# float002.net
KiCad netlist of a schematic drawn in EAGLE
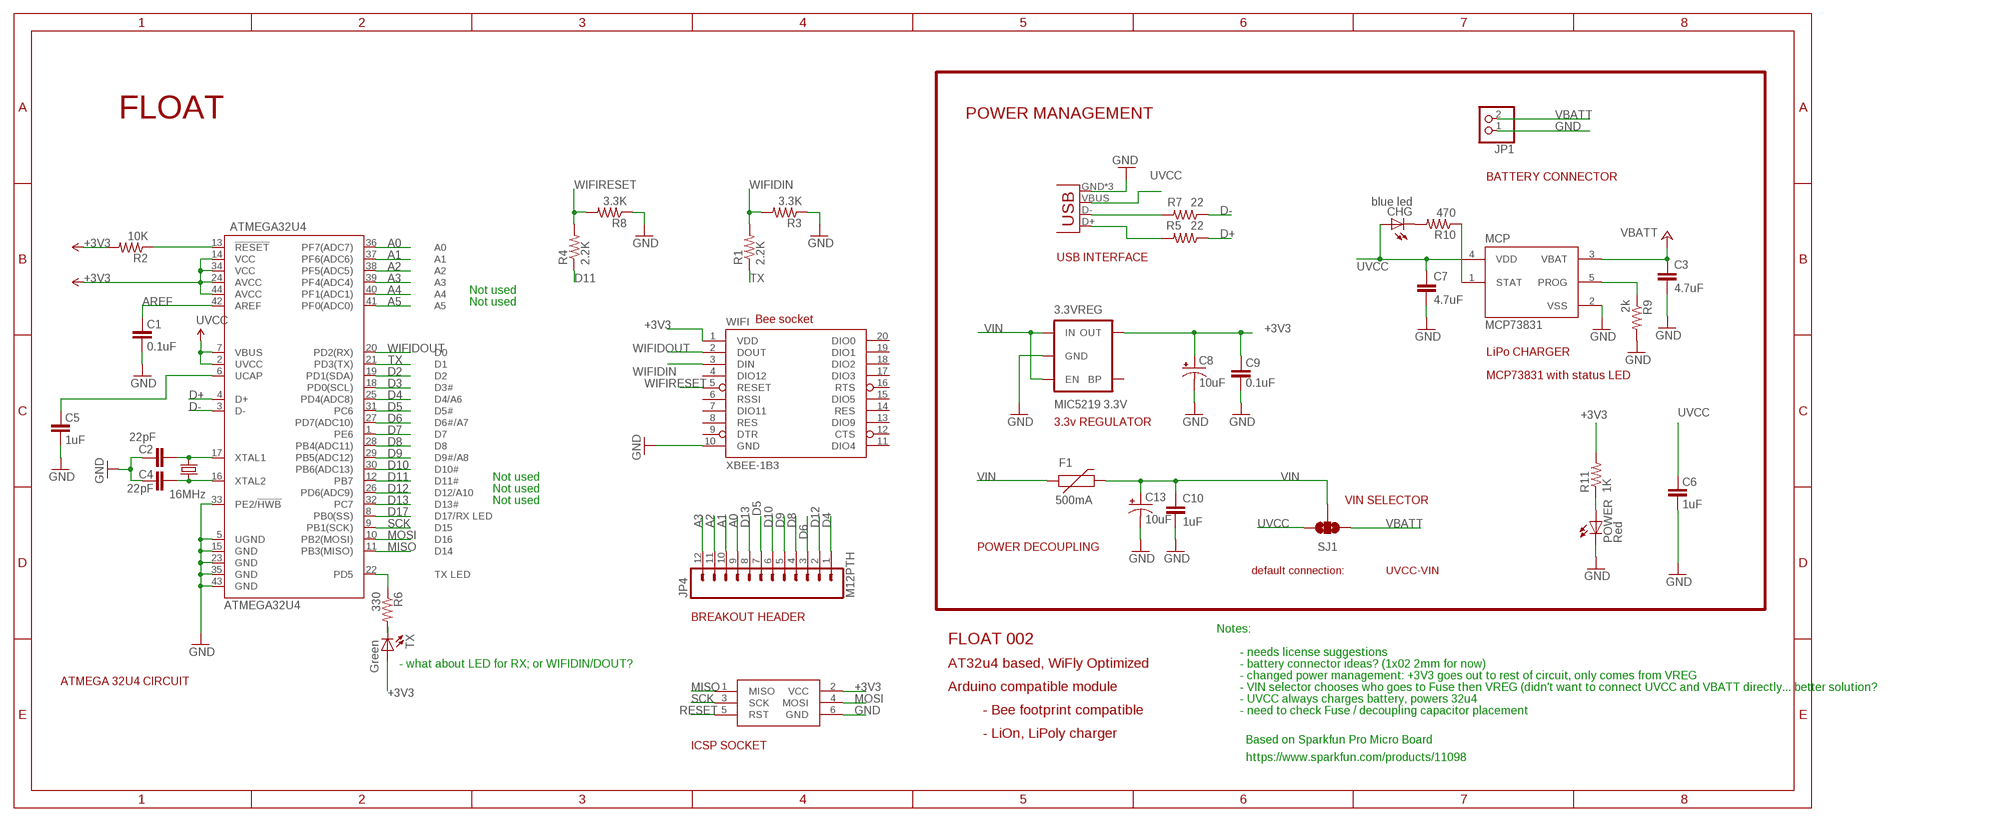
[diagram p0: schematic, sheet 1]

(export (version "E")
  (design (tool "Eeschema 10.0.6"))
  (components
    (comp (ref "3.3VREG")
      (value "MIC5219 3.3V")
      (footprint "eagle-import:SOT23-5")
      (libsource (lib "eagle-import") (part "V_REG_MIC52193.3V"))
    )
    (comp (ref "ATMEGA32U4")
      (value "ATMEGA32U4")
      (footprint "eagle-import:SPARKFUN-DIGITALIC_TQFP44")
      (libsource (lib "eagle-import") (part "ATMEGA32U4TQFP"))
    )
    (comp (ref "C1")
      (value "0.1uF")
      (footprint "eagle-import:0402-CAP")
      (libsource (lib "eagle-import") (part "CAP0402-CAP"))
    )
    (comp (ref "C2")
      (value "22pF")
      (footprint "eagle-import:0402-CAP")
      (libsource (lib "eagle-import") (part "CAP0402-CAP"))
    )
    (comp (ref "C3")
      (value "4.7uF")
      (footprint "eagle-import:0402-CAP")
      (libsource (lib "eagle-import") (part ".1UF-CER"))
    )
    (comp (ref "C4")
      (value "22pF")
      (footprint "eagle-import:0402-CAP")
      (libsource (lib "eagle-import") (part "CAP0402-CAP"))
    )
    (comp (ref "C5")
      (value "1uF")
      (footprint "eagle-import:0402-CAP")
      (libsource (lib "eagle-import") (part "CAP0402-CAP"))
    )
    (comp (ref "C6")
      (value "1uF")
      (footprint "eagle-import:0402-CAP")
      (libsource (lib "eagle-import") (part "CAP0402-CAP"))
    )
    (comp (ref "C7")
      (value "4.7uF")
      (footprint "eagle-import:0402-CAP")
      (libsource (lib "eagle-import") (part ".1UF-CER"))
    )
    (comp (ref "C8")
      (value "10uF")
      (footprint "eagle-import:EIA3216")
      (libsource (lib "eagle-import") (part "CAP_POL1206"))
    )
    (comp (ref "C9")
      (value "0.1uF")
      (footprint "eagle-import:0402-CAP")
      (libsource (lib "eagle-import") (part "CAP0402-CAP"))
    )
    (comp (ref "C10")
      (value "1uF")
      (footprint "eagle-import:0402-CAP")
      (libsource (lib "eagle-import") (part "CAP0402-CAP"))
    )
    (comp (ref "C13")
      (value "10uF")
      (footprint "eagle-import:EIA3216")
      (libsource (lib "eagle-import") (part "CAP_POL1206"))
    )
    (comp (ref "CHG")
      (value "blue led")
      (footprint "eagle-import:CHIP-LED0805")
      (libsource (lib "eagle-import") (part "LEDCHIP-LED0805"))
    )
    (comp (ref "F1")
      (value "500mA")
      (footprint "eagle-import:PTC-1206")
      (libsource (lib "eagle-import") (part "PTCSMD"))
    )
    (comp (ref "ISP1")
      (value "AVRISP-6")
      (footprint "eagle-import:AVRISP")
      (libsource (lib "eagle-import") (part "AVRISP-6"))
    )
    (comp (ref "JP1")
      (value "PINHD-1X2")
      (footprint "eagle-import:1X02")
      (libsource (lib "eagle-import") (part "PINHD-1X2"))
    )
    (comp (ref "JP4")
      (value "M12PTH")
      (footprint "eagle-import:1X12")
      (libsource (lib "eagle-import") (part "M12PTH"))
    )
    (comp (ref "MCP")
      (value "MCP73831")
      (footprint "eagle-import:SOT23-5")
      (libsource (lib "eagle-import") (part "MCP73831"))
    )
    (comp (ref "POWER")
      (value "Red")
      (footprint "eagle-import:LED-0603")
      (libsource (lib "eagle-import") (part "LED0603"))
    )
    (comp (ref "R1")
      (value "2.2K")
      (footprint "eagle-import:0402-RES")
      (libsource (lib "eagle-import") (part "RESISTOR0402-RES"))
    )
    (comp (ref "R2")
      (value "10K")
      (footprint "eagle-import:0402-RES")
      (libsource (lib "eagle-import") (part "RESISTOR0402-RES"))
    )
    (comp (ref "R3")
      (value "3.3K")
      (footprint "eagle-import:0402-RES")
      (libsource (lib "eagle-import") (part "RESISTOR0402-RES"))
    )
    (comp (ref "R4")
      (value "2.2K")
      (footprint "eagle-import:0402-RES")
      (libsource (lib "eagle-import") (part "RESISTOR0402-RES"))
    )
    (comp (ref "R5")
      (value "22")
      (footprint "eagle-import:0402-RES")
      (libsource (lib "eagle-import") (part "RESISTOR0402-RES"))
    )
    (comp (ref "R6")
      (value "330")
      (footprint "eagle-import:0402-RES")
      (libsource (lib "eagle-import") (part "RESISTOR0402-RES"))
    )
    (comp (ref "R7")
      (value "22")
      (footprint "eagle-import:0402-RES")
      (libsource (lib "eagle-import") (part "RESISTOR0402-RES"))
    )
    (comp (ref "R8")
      (value "3.3K")
      (footprint "eagle-import:0402-RES")
      (libsource (lib "eagle-import") (part "RESISTOR0402-RES"))
    )
    (comp (ref "R9")
      (value "2k")
      (footprint "eagle-import:0402-RES")
      (libsource (lib "eagle-import") (part "SparkFun-Resistors_RESISTOR0402-RES"))
    )
    (comp (ref "R10")
      (value "470")
      (footprint "eagle-import:0402-RES")
      (libsource (lib "eagle-import") (part "SparkFun-Resistors_RESISTOR0402-RES"))
    )
    (comp (ref "R11")
      (value "1K")
      (footprint "eagle-import:0402-RES")
      (libsource (lib "eagle-import") (part "RESISTOR0402-RES"))
    )
    (comp (ref "SJ1")
      (value "SOLDERJUMPER_2WAYPASTE1&2")
      (footprint "eagle-import:SJ_3_PASTE1&2")
      (libsource (lib "eagle-import") (part "SOLDERJUMPER_2WAYPASTE1&2"))
    )
    (comp (ref "TX")
      (value "Green")
      (footprint "eagle-import:LED-0603")
      (libsource (lib "eagle-import") (part "LED0603"))
    )
    (comp (ref "WIFI")
      (value "XBEE-1B3")
      (footprint "eagle-import:XBEE-SMD")
      (libsource (lib "eagle-import") (part "XBEE-1B3"))
    )
    (comp (ref "X2")
      (value "USB-MICROB")
      (footprint "eagle-import:USB-MICROB")
      (libsource (lib "eagle-import") (part "USB-MICROB"))
    )
    (comp (ref "Y1")
      (value "16MHz")
      (footprint "eagle-import:CRYSTAL-SMD-5X3")
      (libsource (lib "eagle-import") (part "CRYSTAL5X3"))
    )
  )
  (nets
    (net (code "1") (name "/A0") (class "Default")
      (node (ref "ATMEGA32U4") (pin "36") (pinfunction "PF7(ADC7)_36") (pintype "bidirectional"))
      (node (ref "JP4") (pin "9") (pinfunction "9_9") (pintype "passive"))
    )
    (net (code "2") (name "/A1") (class "Default")
      (node (ref "ATMEGA32U4") (pin "37") (pinfunction "PF6(ADC6)_37") (pintype "bidirectional"))
      (node (ref "JP4") (pin "10") (pinfunction "10_10") (pintype "passive"))
    )
    (net (code "3") (name "/A2") (class "Default")
      (node (ref "ATMEGA32U4") (pin "38") (pinfunction "PF5(ADC5)_38") (pintype "bidirectional"))
      (node (ref "JP4") (pin "11") (pinfunction "11_11") (pintype "passive"))
    )
    (net (code "4") (name "/A3") (class "Default")
      (node (ref "ATMEGA32U4") (pin "39") (pinfunction "PF4(ADC4)_39") (pintype "bidirectional"))
      (node (ref "JP4") (pin "12") (pinfunction "12_12") (pintype "passive"))
    )
    (net (code "5") (name "/A4") (class "Default")
      (node (ref "ATMEGA32U4") (pin "40") (pinfunction "PF1(ADC1)_40") (pintype "bidirectional"))
    )
    (net (code "6") (name "/A5") (class "Default")
      (node (ref "ATMEGA32U4") (pin "41") (pinfunction "PF0(ADC0)_41") (pintype "bidirectional"))
    )
    (net (code "7") (name "/AREF") (class "Default")
      (node (ref "ATMEGA32U4") (pin "42") (pinfunction "AREF_42") (pintype "bidirectional"))
      (node (ref "C1") (pin "2") (pinfunction "2_2") (pintype "passive"))
    )
    (net (code "8") (name "/D+") (class "Default")
      (node (ref "ATMEGA32U4") (pin "4") (pinfunction "D+_4") (pintype "bidirectional"))
      (node (ref "R5") (pin "1") (pinfunction "1_1") (pintype "passive"))
    )
    (net (code "9") (name "/D-") (class "Default")
      (node (ref "ATMEGA32U4") (pin "3") (pinfunction "D-_3") (pintype "bidirectional"))
      (node (ref "R7") (pin "1") (pinfunction "1_1") (pintype "passive"))
    )
    (net (code "10") (name "/D2") (class "Default")
      (node (ref "ATMEGA32U4") (pin "19") (pinfunction "PD1(SDA)_19") (pintype "bidirectional"))
    )
    (net (code "11") (name "/D3") (class "Default")
      (node (ref "ATMEGA32U4") (pin "18") (pinfunction "PD0(SCL)_18") (pintype "bidirectional"))
    )
    (net (code "12") (name "/D4") (class "Default")
      (node (ref "ATMEGA32U4") (pin "25") (pinfunction "PD4(ADC8)_25") (pintype "bidirectional"))
      (node (ref "JP4") (pin "1") (pinfunction "1_1") (pintype "passive"))
    )
    (net (code "13") (name "/D5") (class "Default")
      (node (ref "ATMEGA32U4") (pin "31") (pinfunction "PC6_31") (pintype "bidirectional"))
      (node (ref "JP4") (pin "7") (pinfunction "7_7") (pintype "passive"))
    )
    (net (code "14") (name "/D6") (class "Default")
      (node (ref "ATMEGA32U4") (pin "27") (pinfunction "PD7(ADC10)_27") (pintype "bidirectional"))
      (node (ref "JP4") (pin "3") (pinfunction "3_3") (pintype "passive"))
    )
    (net (code "15") (name "/D7") (class "Default")
      (node (ref "ATMEGA32U4") (pin "1") (pinfunction "PE6_1") (pintype "bidirectional"))
    )
    (net (code "16") (name "/D8") (class "Default")
      (node (ref "ATMEGA32U4") (pin "28") (pinfunction "PB4(ADC11)_28") (pintype "bidirectional"))
      (node (ref "JP4") (pin "4") (pinfunction "4_4") (pintype "passive"))
    )
    (net (code "17") (name "/D9") (class "Default")
      (node (ref "ATMEGA32U4") (pin "29") (pinfunction "PB5(ADC12)_29") (pintype "bidirectional"))
      (node (ref "JP4") (pin "5") (pinfunction "5_5") (pintype "passive"))
    )
    (net (code "18") (name "/D10") (class "Default")
      (node (ref "ATMEGA32U4") (pin "30") (pinfunction "PB6(ADC13)_30") (pintype "bidirectional"))
      (node (ref "JP4") (pin "6") (pinfunction "6_6") (pintype "passive"))
    )
    (net (code "19") (name "/D11") (class "Default")
      (node (ref "ATMEGA32U4") (pin "12") (pinfunction "PB7_12") (pintype "bidirectional"))
      (node (ref "R4") (pin "1") (pinfunction "1_1") (pintype "passive"))
    )
    (net (code "20") (name "/D12") (class "Default")
      (node (ref "ATMEGA32U4") (pin "26") (pinfunction "PD6(ADC9)_26") (pintype "bidirectional"))
      (node (ref "JP4") (pin "2") (pinfunction "2_2") (pintype "passive"))
    )
    (net (code "21") (name "/D13") (class "Default")
      (node (ref "ATMEGA32U4") (pin "32") (pinfunction "PC7_32") (pintype "bidirectional"))
      (node (ref "JP4") (pin "8") (pinfunction "8_8") (pintype "passive"))
    )
    (net (code "22") (name "/D17") (class "Default")
      (node (ref "ATMEGA32U4") (pin "8") (pinfunction "PB0(SS)_8") (pintype "bidirectional"))
    )
    (net (code "23") (name "/MISO") (class "Default")
      (node (ref "ATMEGA32U4") (pin "11") (pinfunction "PB3(MISO)_11") (pintype "bidirectional"))
      (node (ref "ISP1") (pin "1") (pinfunction "MISO_1") (pintype "input"))
    )
    (net (code "24") (name "/MOSI") (class "Default")
      (node (ref "ATMEGA32U4") (pin "10") (pinfunction "PB2(MOSI)_10") (pintype "bidirectional"))
      (node (ref "ISP1") (pin "4") (pinfunction "MOSI_4") (pintype "output"))
    )
    (net (code "25") (name "/RESET") (class "Default")
      (node (ref "ATMEGA32U4") (pin "13") (pinfunction "~{RESET}_13") (pintype "bidirectional"))
      (node (ref "ISP1") (pin "5") (pinfunction "RST_5") (pintype "output"))
      (node (ref "R2") (pin "1") (pinfunction "1_1") (pintype "passive"))
    )
    (net (code "26") (name "/SCK") (class "Default")
      (node (ref "ATMEGA32U4") (pin "9") (pinfunction "PB1(SCK)_9") (pintype "bidirectional"))
      (node (ref "ISP1") (pin "3") (pinfunction "SCK_3") (pintype "output"))
    )
    (net (code "27") (name "/TX") (class "Default")
      (node (ref "ATMEGA32U4") (pin "21") (pinfunction "PD3(TX)_21") (pintype "bidirectional"))
      (node (ref "R1") (pin "1") (pinfunction "1_1") (pintype "passive"))
    )
    (net (code "28") (name "/VIN") (class "Default")
      (node (ref "3.3VREG") (pin "1") (pinfunction "IN_1") (pintype "input"))
      (node (ref "3.3VREG") (pin "3") (pinfunction "EN_3") (pintype "input"))
      (node (ref "C10") (pin "1") (pinfunction "1_1") (pintype "passive"))
      (node (ref "C13") (pin "A") (pinfunction "+_A") (pintype "passive"))
      (node (ref "F1") (pin "1") (pinfunction "1_1") (pintype "bidirectional"))
      (node (ref "F1") (pin "2") (pinfunction "2_2") (pintype "bidirectional"))
      (node (ref "SJ1") (pin "2") (pinfunction "2_2") (pintype "passive"))
    )
    (net (code "29") (name "/WIFIDIN") (class "Default")
      (node (ref "R1") (pin "2") (pinfunction "2_2") (pintype "passive"))
      (node (ref "R3") (pin "2") (pinfunction "2_2") (pintype "passive"))
      (node (ref "WIFI") (pin "3") (pinfunction "DIN_3") (pintype "input"))
    )
    (net (code "30") (name "/WIFIDOUT") (class "Default")
      (node (ref "ATMEGA32U4") (pin "20") (pinfunction "PD2(RX)_20") (pintype "bidirectional"))
      (node (ref "WIFI") (pin "2") (pinfunction "DOUT_2") (pintype "output"))
    )
    (net (code "31") (name "/WIFIRESET") (class "Default")
      (node (ref "R4") (pin "2") (pinfunction "2_2") (pintype "passive"))
      (node (ref "R8") (pin "2") (pinfunction "2_2") (pintype "passive"))
      (node (ref "WIFI") (pin "5") (pinfunction "RESET_5") (pintype "input"))
    )
    (net (code "32") (name "GND") (class "Default")
      (node (ref "3.3VREG") (pin "2") (pinfunction "GND_2") (pintype "input"))
      (node (ref "ATMEGA32U4") (pin "15") (pinfunction "GND_15") (pintype "bidirectional"))
      (node (ref "ATMEGA32U4") (pin "23") (pinfunction "GND_23") (pintype "bidirectional"))
      (node (ref "ATMEGA32U4") (pin "33") (pinfunction "PE2/~{HWB}_33") (pintype "bidirectional"))
      (node (ref "ATMEGA32U4") (pin "35") (pinfunction "GND_35") (pintype "bidirectional"))
      (node (ref "ATMEGA32U4") (pin "43") (pinfunction "GND_43") (pintype "bidirectional"))
      (node (ref "ATMEGA32U4") (pin "5") (pinfunction "UGND_5") (pintype "bidirectional"))
      (node (ref "C1") (pin "1") (pinfunction "1_1") (pintype "passive"))
      (node (ref "C10") (pin "2") (pinfunction "2_2") (pintype "passive"))
      (node (ref "C13") (pin "C") (pinfunction "-_C") (pintype "passive"))
      (node (ref "C2") (pin "2") (pinfunction "2_2") (pintype "passive"))
      (node (ref "C3") (pin "2") (pinfunction "2_2") (pintype "passive"))
      (node (ref "C4") (pin "2") (pinfunction "2_2") (pintype "passive"))
      (node (ref "C5") (pin "1") (pinfunction "1_1") (pintype "passive"))
      (node (ref "C6") (pin "1") (pinfunction "1_1") (pintype "passive"))
      (node (ref "C7") (pin "2") (pinfunction "2_2") (pintype "passive"))
      (node (ref "C8") (pin "C") (pinfunction "-_C") (pintype "passive"))
      (node (ref "C9") (pin "1") (pinfunction "1_1") (pintype "passive"))
      (node (ref "ISP1") (pin "6") (pinfunction "GND_6") (pintype "power_in"))
      (node (ref "JP1") (pin "1") (pinfunction "1_1") (pintype "passive"))
      (node (ref "MCP") (pin "2") (pinfunction "VSS_2") (pintype "bidirectional"))
      (node (ref "POWER") (pin "C") (pinfunction "C_C") (pintype "passive"))
      (node (ref "R3") (pin "1") (pinfunction "1_1") (pintype "passive"))
      (node (ref "R8") (pin "1") (pinfunction "1_1") (pintype "passive"))
      (node (ref "R9") (pin "2") (pinfunction "2_2") (pintype "passive"))
      (node (ref "WIFI") (pin "10") (pinfunction "GND_10") (pintype "power_in"))
      (node (ref "X2") (pin "GND") (pinfunction "GND_GND") (pintype "bidirectional"))
      (node (ref "X2") (pin "MT1") (pinfunction "GND_MT1") (pintype "bidirectional"))
      (node (ref "X2") (pin "MT2") (pinfunction "GND_MT2") (pintype "bidirectional"))
    )
    (net (code "33") (name "Net-(ATMEGA32U4-PD5)") (class "Default")
      (node (ref "ATMEGA32U4") (pin "22") (pinfunction "PD5_22") (pintype "bidirectional"))
      (node (ref "R6") (pin "1") (pinfunction "1_1") (pintype "passive"))
    )
    (net (code "34") (name "Net-(ATMEGA32U4-UCAP)") (class "Default")
      (node (ref "ATMEGA32U4") (pin "6") (pinfunction "UCAP_6") (pintype "bidirectional"))
      (node (ref "C5") (pin "2") (pinfunction "2_2") (pintype "passive"))
    )
    (net (code "35") (name "Net-(ATMEGA32U4-XTAL1)") (class "Default")
      (node (ref "ATMEGA32U4") (pin "17") (pinfunction "XTAL1_17") (pintype "bidirectional"))
      (node (ref "C2") (pin "1") (pinfunction "1_1") (pintype "passive"))
      (node (ref "Y1") (pin "3") (pinfunction "2_3") (pintype "passive"))
    )
    (net (code "36") (name "Net-(ATMEGA32U4-XTAL2)") (class "Default")
      (node (ref "ATMEGA32U4") (pin "16") (pinfunction "XTAL2_16") (pintype "bidirectional"))
      (node (ref "C4") (pin "1") (pinfunction "1_1") (pintype "passive"))
      (node (ref "Y1") (pin "1") (pinfunction "1_1") (pintype "passive"))
    )
    (net (code "37") (name "Net-(CHG-PadC)") (class "Default")
      (node (ref "CHG") (pin "C") (pinfunction "C_C") (pintype "passive"))
      (node (ref "R10") (pin "2") (pinfunction "2_2") (pintype "passive"))
    )
    (net (code "38") (name "Net-(MCP-PROG)") (class "Default")
      (node (ref "MCP") (pin "5") (pinfunction "PROG_5") (pintype "bidirectional"))
      (node (ref "R9") (pin "1") (pinfunction "1_1") (pintype "passive"))
    )
    (net (code "39") (name "Net-(MCP-STAT)") (class "Default")
      (node (ref "MCP") (pin "1") (pinfunction "STAT_1") (pintype "bidirectional"))
      (node (ref "R10") (pin "1") (pinfunction "1_1") (pintype "passive"))
    )
    (net (code "40") (name "Net-(POWER-PadA)") (class "Default")
      (node (ref "POWER") (pin "A") (pinfunction "A_A") (pintype "passive"))
      (node (ref "R11") (pin "1") (pinfunction "1_1") (pintype "passive"))
    )
    (net (code "41") (name "Net-(R5-Pad2)") (class "Default")
      (node (ref "R5") (pin "2") (pinfunction "2_2") (pintype "passive"))
      (node (ref "X2") (pin "D+") (pinfunction "D+_D+") (pintype "bidirectional"))
    )
    (net (code "42") (name "Net-(R6-Pad2)") (class "Default")
      (node (ref "R6") (pin "2") (pinfunction "2_2") (pintype "passive"))
      (node (ref "TX") (pin "C") (pinfunction "C_C") (pintype "passive"))
    )
    (net (code "43") (name "Net-(R7-Pad2)") (class "Default")
      (node (ref "R7") (pin "2") (pinfunction "2_2") (pintype "passive"))
      (node (ref "X2") (pin "D-") (pinfunction "D-_D-") (pintype "bidirectional"))
    )
    (net (code "44") (name "UVCC") (class "Default")
      (node (ref "ATMEGA32U4") (pin "2") (pinfunction "UVCC_2") (pintype "bidirectional"))
      (node (ref "ATMEGA32U4") (pin "7") (pinfunction "VBUS_7") (pintype "bidirectional"))
      (node (ref "C6") (pin "2") (pinfunction "2_2") (pintype "passive"))
      (node (ref "C7") (pin "1") (pinfunction "1_1") (pintype "passive"))
      (node (ref "CHG") (pin "A") (pinfunction "A_A") (pintype "passive"))
      (node (ref "MCP") (pin "4") (pinfunction "VDD_4") (pintype "bidirectional"))
      (node (ref "SJ1") (pin "3") (pinfunction "3_3") (pintype "passive"))
      (node (ref "X2") (pin "VBUS") (pinfunction "VBUS_VBUS") (pintype "bidirectional"))
    )
    (net (code "45") (name "VBATT") (class "Default")
      (node (ref "C3") (pin "1") (pinfunction "1_1") (pintype "passive"))
      (node (ref "JP1") (pin "2") (pinfunction "2_2") (pintype "passive"))
      (node (ref "MCP") (pin "3") (pinfunction "VBAT_3") (pintype "bidirectional"))
      (node (ref "SJ1") (pin "1") (pinfunction "1_1") (pintype "passive"))
    )
    (net (code "46") (name "VCC") (class "Default")
      (node (ref "3.3VREG") (pin "5") (pinfunction "OUT_5") (pintype "passive"))
      (node (ref "ATMEGA32U4") (pin "14") (pinfunction "VCC_14") (pintype "bidirectional"))
      (node (ref "ATMEGA32U4") (pin "24") (pinfunction "AVCC_24") (pintype "bidirectional"))
      (node (ref "ATMEGA32U4") (pin "34") (pinfunction "VCC_34") (pintype "bidirectional"))
      (node (ref "ATMEGA32U4") (pin "44") (pinfunction "AVCC_44") (pintype "bidirectional"))
      (node (ref "C8") (pin "A") (pinfunction "+_A") (pintype "passive"))
      (node (ref "C9") (pin "2") (pinfunction "2_2") (pintype "passive"))
      (node (ref "ISP1") (pin "2") (pinfunction "VCC_2") (pintype "power_in"))
      (node (ref "R11") (pin "2") (pinfunction "2_2") (pintype "passive"))
      (node (ref "R2") (pin "2") (pinfunction "2_2") (pintype "passive"))
      (node (ref "TX") (pin "A") (pinfunction "A_A") (pintype "passive"))
      (node (ref "WIFI") (pin "1") (pinfunction "VDD_1") (pintype "power_in"))
    )
    (net (code "47") (name "unconnected-(3.3VREG-BP-Pad4)") (class "Default")
      (node (ref "3.3VREG") (pin "4") (pinfunction "BP_4") (pintype "input"))
    )
    (net (code "48") (name "unconnected-(WIFI-CTS-Pad12)") (class "Default")
      (node (ref "WIFI") (pin "12") (pinfunction "CTS_12") (pintype "output"))
    )
    (net (code "49") (name "unconnected-(WIFI-DIO0-Pad20)") (class "Default")
      (node (ref "WIFI") (pin "20") (pinfunction "DIO0_20") (pintype "bidirectional"))
    )
    (net (code "50") (name "unconnected-(WIFI-DIO1-Pad19)") (class "Default")
      (node (ref "WIFI") (pin "19") (pinfunction "DIO1_19") (pintype "bidirectional"))
    )
    (net (code "51") (name "unconnected-(WIFI-DIO2-Pad18)") (class "Default")
      (node (ref "WIFI") (pin "18") (pinfunction "DIO2_18") (pintype "bidirectional"))
    )
    (net (code "52") (name "unconnected-(WIFI-DIO3-Pad17)") (class "Default")
      (node (ref "WIFI") (pin "17") (pinfunction "DIO3_17") (pintype "bidirectional"))
    )
    (net (code "53") (name "unconnected-(WIFI-DIO4-Pad11)") (class "Default")
      (node (ref "WIFI") (pin "11") (pinfunction "DIO4_11") (pintype "bidirectional"))
    )
    (net (code "54") (name "unconnected-(WIFI-DIO5-Pad15)") (class "Default")
      (node (ref "WIFI") (pin "15") (pinfunction "DIO5_15") (pintype "bidirectional"))
    )
    (net (code "55") (name "unconnected-(WIFI-DIO9-Pad13)") (class "Default")
      (node (ref "WIFI") (pin "13") (pinfunction "DIO9_13") (pintype "bidirectional"))
    )
    (net (code "56") (name "unconnected-(WIFI-DIO11-Pad7)") (class "Default")
      (node (ref "WIFI") (pin "7") (pinfunction "DIO11_7") (pintype "bidirectional"))
    )
    (net (code "57") (name "unconnected-(WIFI-DIO12-Pad4)") (class "Default")
      (node (ref "WIFI") (pin "4") (pinfunction "DIO12_4") (pintype "bidirectional"))
    )
    (net (code "58") (name "unconnected-(WIFI-DTR-Pad9)") (class "Default")
      (node (ref "WIFI") (pin "9") (pinfunction "DTR_9") (pintype "bidirectional"))
    )
    (net (code "59") (name "unconnected-(WIFI-RES-Pad8)") (class "Default")
      (node (ref "WIFI") (pin "8") (pinfunction "RES_8") (pintype "bidirectional"))
    )
    (net (code "60") (name "unconnected-(WIFI-RES-Pad14)") (class "Default")
      (node (ref "WIFI") (pin "14") (pinfunction "RES_14") (pintype "bidirectional"))
    )
    (net (code "61") (name "unconnected-(WIFI-RSSI-Pad6)") (class "Default")
      (node (ref "WIFI") (pin "6") (pinfunction "RSSI_6") (pintype "bidirectional"))
    )
    (net (code "62") (name "unconnected-(WIFI-RTS-Pad16)") (class "Default")
      (node (ref "WIFI") (pin "16") (pinfunction "RTS_16") (pintype "input"))
    )
  )
)
